# BreakBeamReceiver.net
KiCad netlist of a schematic drawn in EAGLE
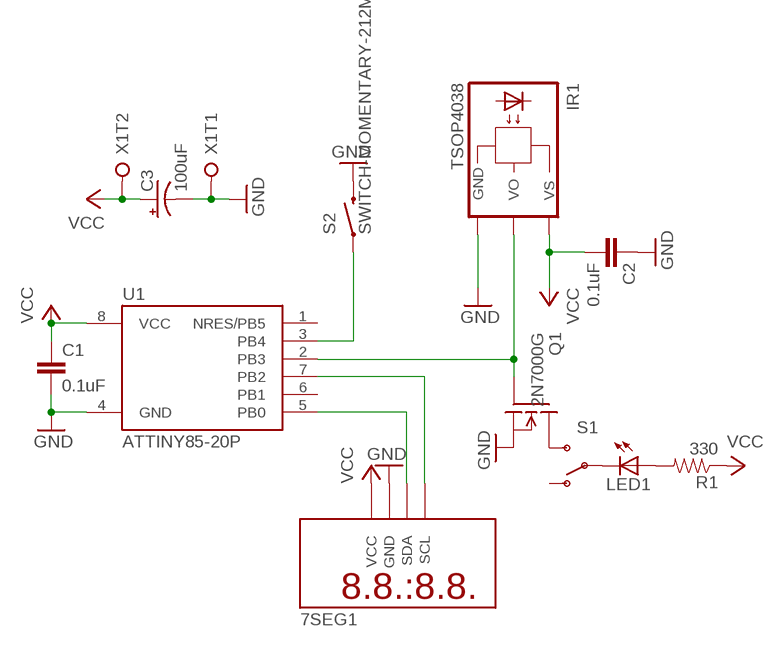
[diagram p0: schematic, sheet 1]

(export (version "E")
  (design (tool "Eeschema 10.0.6"))
  (components
    (comp (ref "7SEG1")
      (value "7-SEGMENT-BACKPACK")
      (footprint "eagle-import:7-SEGMENT-BACKPACK")
      (libsource (lib "eagle-import") (part "7-SEGMENT-BACKPACK"))
    )
    (comp (ref "C1")
      (value "0.1uF")
      (footprint "eagle-import:CAPACITOR-5MM")
      (libsource (lib "eagle-import") (part "CAPACITOR-5MM"))
    )
    (comp (ref "C2")
      (value "0.1uF")
      (footprint "eagle-import:CAPACITOR-5MM")
      (libsource (lib "eagle-import") (part "CAPACITOR-5MM"))
    )
    (comp (ref "C3")
      (value "100uF")
      (footprint "eagle-import:CPOL-RADIAL-100UF-25V")
      (libsource (lib "eagle-import") (part "CAP_POLPTH1"))
    )
    (comp (ref "IR1")
      (value "TSOP4038")
      (footprint "eagle-import:TSOP")
      (libsource (lib "eagle-import") (part "TSOP4038"))
    )
    (comp (ref "LED1")
      (value "LED5MM")
      (footprint "eagle-import:LED5MM")
      (libsource (lib "eagle-import") (part "LED5MM"))
    )
    (comp (ref "Q1")
      (value "2N7000G")
      (footprint "eagle-import:TO92-INLINE")
      (libsource (lib "eagle-import") (part "2N7000G"))
    )
    (comp (ref "R1")
      (value "330")
      (footprint "eagle-import:AXIAL-5MM")
      (libsource (lib "eagle-import") (part "RESISTOR-5MM"))
    )
    (comp (ref "S1")
      (value "SWITCH-SPDTPTH")
      (footprint "eagle-import:SWITCH-SPDT")
      (libsource (lib "eagle-import") (part "SWITCH-SPDTPTH"))
    )
    (comp (ref "S2")
      (value "SWITCH-MOMENTARY-212MM")
      (footprint "eagle-import:TACTILE-PTH-12MM")
      (libsource (lib "eagle-import") (part "SWITCH-MOMENTARY-212MM"))
    )
    (comp (ref "U1")
      (value "ATTINY85-20P")
      (footprint "eagle-import:PDIP08_300MIL")
      (libsource (lib "eagle-import") (part "ATTINY85P-20"))
    )
    (comp (ref "X1")
      (value "SCREW-TERM-2")
      (footprint "eagle-import:SCREW-TERM-2")
      (libsource (lib "eagle-import") (part "SCREW-TERM-2"))
    )
  )
  (nets
    (net (code "1") (name "GND") (class "Default")
      (node (ref "7SEG1") (pin "GND") (pinfunction "GND_GND") (pintype "power_in"))
      (node (ref "C1") (pin "2") (pinfunction "2_2") (pintype "passive"))
      (node (ref "C2") (pin "1") (pinfunction "1_1") (pintype "passive"))
      (node (ref "C3") (pin "2") (pinfunction "-_2") (pintype "passive"))
      (node (ref "IR1") (pin "GND") (pinfunction "GND_GND") (pintype "power_in"))
      (node (ref "Q1") (pin "1") (pinfunction "SRC_1") (pintype "passive"))
      (node (ref "S2") (pin "3") (pinfunction "2_3") (pintype "passive"))
      (node (ref "U1") (pin "4") (pinfunction "GND_4") (pintype "power_in"))
      (node (ref "X1") (pin "1") (pinfunction "KL_1") (pintype "passive"))
    )
    (net (code "2") (name "Net-(LED1-C)") (class "Default")
      (node (ref "LED1") (pin "K") (pinfunction "C_K") (pintype "passive"))
      (node (ref "S1") (pin "2") (pinfunction "P_2") (pintype "passive"))
    )
    (net (code "3") (name "Net-(Q1-DRN)") (class "Default")
      (node (ref "Q1") (pin "3") (pinfunction "DRN_3") (pintype "passive"))
      (node (ref "S1") (pin "3") (pinfunction "S_3") (pintype "passive"))
    )
    (net (code "4") (name "Net-(Q1-GATE)") (class "Default")
      (node (ref "IR1") (pin "VO") (pinfunction "VO_VO") (pintype "open_collector"))
      (node (ref "Q1") (pin "2") (pinfunction "GATE_2") (pintype "passive"))
      (node (ref "U1") (pin "2") (pinfunction "PB3_2") (pintype "bidirectional"))
    )
    (net (code "5") (name "Net-(R1-2)") (class "Default")
      (node (ref "LED1") (pin "A") (pinfunction "A_A") (pintype "passive"))
      (node (ref "R1") (pin "P$2") (pinfunction "2_P$2") (pintype "passive"))
    )
    (net (code "6") (name "Net-(U1-PB0)") (class "Default")
      (node (ref "7SEG1") (pin "SDA") (pinfunction "SDA_SDA") (pintype "bidirectional"))
      (node (ref "U1") (pin "5") (pinfunction "PB0_5") (pintype "bidirectional"))
    )
    (net (code "7") (name "Net-(U1-PB2)") (class "Default")
      (node (ref "7SEG1") (pin "SCL") (pinfunction "SCL_SCL") (pintype "bidirectional"))
      (node (ref "U1") (pin "7") (pinfunction "PB2_7") (pintype "bidirectional"))
    )
    (net (code "8") (name "Net-(U1-PB4)") (class "Default")
      (node (ref "S2") (pin "1") (pinfunction "1_1") (pintype "passive"))
      (node (ref "U1") (pin "3") (pinfunction "PB4_3") (pintype "bidirectional"))
    )
    (net (code "9") (name "VCC") (class "Default")
      (node (ref "7SEG1") (pin "VCC") (pinfunction "VCC_VCC") (pintype "power_in"))
      (node (ref "C1") (pin "1") (pinfunction "1_1") (pintype "passive"))
      (node (ref "C2") (pin "2") (pinfunction "2_2") (pintype "passive"))
      (node (ref "C3") (pin "1") (pinfunction "+_1") (pintype "passive"))
      (node (ref "IR1") (pin "VS") (pinfunction "VS_VS") (pintype "power_in"))
      (node (ref "R1") (pin "P$1") (pinfunction "1_P$1") (pintype "passive"))
      (node (ref "U1") (pin "8") (pinfunction "VCC_8") (pintype "power_in"))
      (node (ref "X1") (pin "2") (pinfunction "KL_2") (pintype "passive"))
    )
    (net (code "10") (name "unconnected-(S1-O-Pad1)") (class "Default")
      (node (ref "S1") (pin "1") (pinfunction "O_1") (pintype "passive"))
    )
    (net (code "11") (name "unconnected-(U1-NRES{slash}PB5-Pad1)") (class "Default")
      (node (ref "U1") (pin "1") (pinfunction "NRES/PB5_1") (pintype "bidirectional"))
    )
    (net (code "12") (name "unconnected-(U1-PB1-Pad6)") (class "Default")
      (node (ref "U1") (pin "6") (pinfunction "PB1_6") (pintype "bidirectional"))
    )
  )
)
